# Sources.net
KiCad netlist of a schematic drawn in Altium Designer
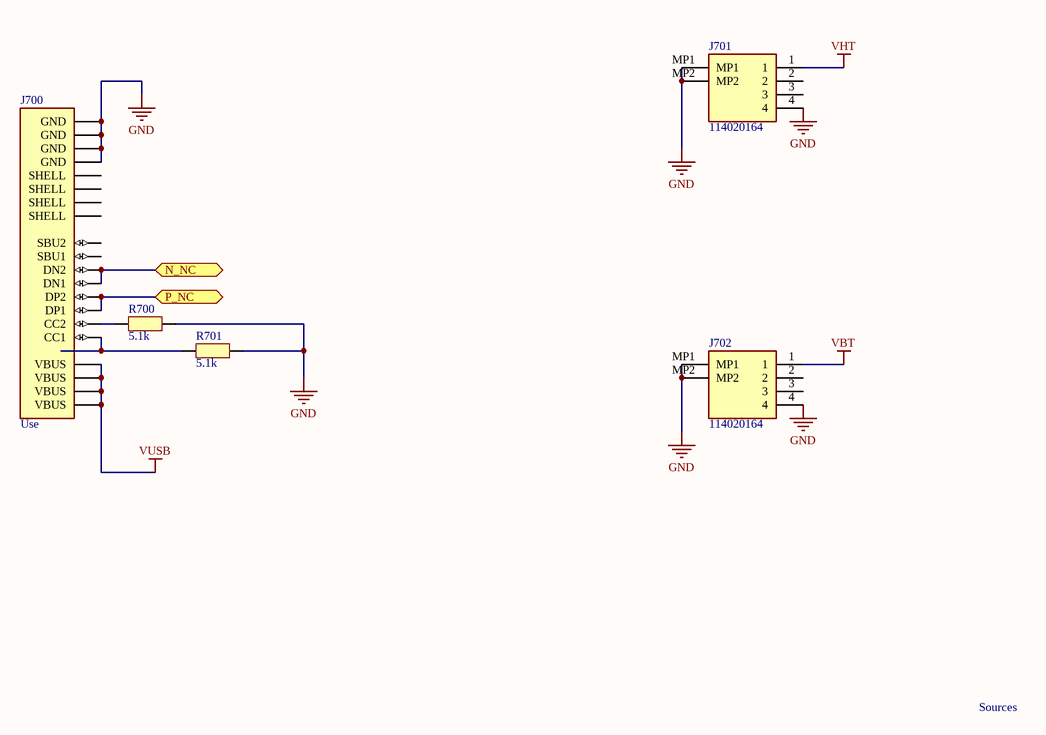
[diagram p0: Sources.SchDoc]

(export (version "E")
  (design (tool "Eeschema 10.0.6"))
  (components
    (comp (ref "J700")
      (value "Use")
      (footprint "USB4085-GF-A")
      (description "Connecteurs USB USB Type C, 2.0, Rec, TH , G/F, RA , Top Mnt, T & R")
      (libsource (lib "SCHLibrary") (part "USB4085-GF-A"))
    )
    (comp (ref "J701")
      (value "114020164")
      (footprint "114020164")
      (description "Seeed Studio Accessories Grove Female Header - SMD-4P-2.0mm-90D-20Pcs")
      (fields (field (name "MOUSER PART NUMBER") "713-114020164"))
      (libsource (lib "SCHLibrary") (part "114020164"))
    )
    (comp (ref "J702")
      (value "114020164")
      (footprint "114020164")
      (description "Seeed Studio Accessories Grove Female Header - SMD-4P-2.0mm-90D-20Pcs")
      (fields (field (name "MOUSER PART NUMBER") "713-114020164"))
      (libsource (lib "SCHLibrary") (part "114020164"))
    )
    (comp (ref "R700")
      (value "5.1k")
      (footprint "RESC1005X06N")
      (libsource (lib "SCHLibrary") (part "Resistor"))
    )
    (comp (ref "R701")
      (value "5.1k")
      (footprint "RESC1005X06N")
      (libsource (lib "SCHLibrary") (part "Resistor"))
    )
  )
  (nets
    (net (code "1") (name "/N_NC") (class "Default")
      (node (ref "J700") (pin "A7") (pinfunction "DN1_A7") (pintype "bidirectional"))
      (node (ref "J700") (pin "B7") (pinfunction "DN2_B7") (pintype "bidirectional"))
    )
    (net (code "2") (name "/P_NC") (class "Default")
      (node (ref "J700") (pin "A6") (pinfunction "DP1_A6") (pintype "bidirectional"))
      (node (ref "J700") (pin "B6") (pinfunction "DP2_B6") (pintype "bidirectional"))
    )
    (net (code "3") (name "GND") (class "Default")
      (node (ref "J700") (pin "A1") (pinfunction "GND_A1") (pintype "power_in"))
      (node (ref "J700") (pin "A12") (pinfunction "GND_A12") (pintype "power_in"))
      (node (ref "J700") (pin "B1") (pinfunction "GND_B1") (pintype "power_in"))
      (node (ref "J700") (pin "B12") (pinfunction "GND_B12") (pintype "power_in"))
      (node (ref "J701") (pin "4") (pinfunction "4_4") (pintype "passive"))
      (node (ref "J701") (pin "MP1") (pinfunction "MP1_MP1") (pintype "passive"))
      (node (ref "J701") (pin "MP2") (pinfunction "MP2_MP2") (pintype "passive"))
      (node (ref "J702") (pin "4") (pinfunction "4_4") (pintype "passive"))
      (node (ref "J702") (pin "MP1") (pinfunction "MP1_MP1") (pintype "passive"))
      (node (ref "J702") (pin "MP2") (pinfunction "MP2_MP2") (pintype "passive"))
      (node (ref "R700") (pin "2") (pinfunction "2_2") (pintype "passive"))
      (node (ref "R701") (pin "2") (pinfunction "2_2") (pintype "passive"))
    )
    (net (code "4") (name "Net-(J700-CC1)") (class "Default")
      (node (ref "J700") (pin "A5") (pinfunction "CC1_A5") (pintype "bidirectional"))
      (node (ref "R701") (pin "1") (pinfunction "1_1") (pintype "passive"))
    )
    (net (code "5") (name "Net-(J700-CC2)") (class "Default")
      (node (ref "J700") (pin "B5") (pinfunction "CC2_B5") (pintype "bidirectional"))
      (node (ref "R700") (pin "1") (pinfunction "1_1") (pintype "passive"))
    )
    (net (code "6") (name "VBT") (class "Default")
      (node (ref "J702") (pin "1") (pinfunction "1_1") (pintype "passive"))
    )
    (net (code "7") (name "VHT") (class "Default")
      (node (ref "J701") (pin "1") (pinfunction "1_1") (pintype "passive"))
    )
    (net (code "8") (name "VUSB") (class "Default")
      (node (ref "J700") (pin "A4") (pinfunction "VBUS_A4") (pintype "power_in"))
      (node (ref "J700") (pin "A9") (pinfunction "VBUS_A9") (pintype "power_in"))
      (node (ref "J700") (pin "B4") (pinfunction "VBUS_B4") (pintype "power_in"))
      (node (ref "J700") (pin "B9") (pinfunction "VBUS_B9") (pintype "power_in"))
    )
    (net (code "9") (name "unconnected-(J700-SBU1-PadA8)") (class "Default")
      (node (ref "J700") (pin "A8") (pinfunction "SBU1_A8") (pintype "bidirectional"))
    )
    (net (code "10") (name "unconnected-(J700-SBU2-PadB8)") (class "Default")
      (node (ref "J700") (pin "B8") (pinfunction "SBU2_B8") (pintype "bidirectional"))
    )
    (net (code "11") (name "unconnected-(J700-SHELL-PadS1)") (class "Default")
      (node (ref "J700") (pin "S1") (pinfunction "SHELL_S1") (pintype "passive"))
    )
    (net (code "12") (name "unconnected-(J700-SHELL-PadS2)") (class "Default")
      (node (ref "J700") (pin "S2") (pinfunction "SHELL_S2") (pintype "passive"))
    )
    (net (code "13") (name "unconnected-(J700-SHELL-PadS3)") (class "Default")
      (node (ref "J700") (pin "S3") (pinfunction "SHELL_S3") (pintype "passive"))
    )
    (net (code "14") (name "unconnected-(J700-SHELL-PadS4)") (class "Default")
      (node (ref "J700") (pin "S4") (pinfunction "SHELL_S4") (pintype "passive"))
    )
    (net (code "15") (name "unconnected-(J701-Pad2)") (class "Default")
      (node (ref "J701") (pin "2") (pinfunction "2_2") (pintype "passive"))
    )
    (net (code "16") (name "unconnected-(J701-Pad3)") (class "Default")
      (node (ref "J701") (pin "3") (pinfunction "3_3") (pintype "passive"))
    )
    (net (code "17") (name "unconnected-(J702-Pad2)") (class "Default")
      (node (ref "J702") (pin "2") (pinfunction "2_2") (pintype "passive"))
    )
    (net (code "18") (name "unconnected-(J702-Pad3)") (class "Default")
      (node (ref "J702") (pin "3") (pinfunction "3_3") (pintype "passive"))
    )
  )
)
